# 02_Power.net
KiCad netlist of a schematic drawn in Altium Designer
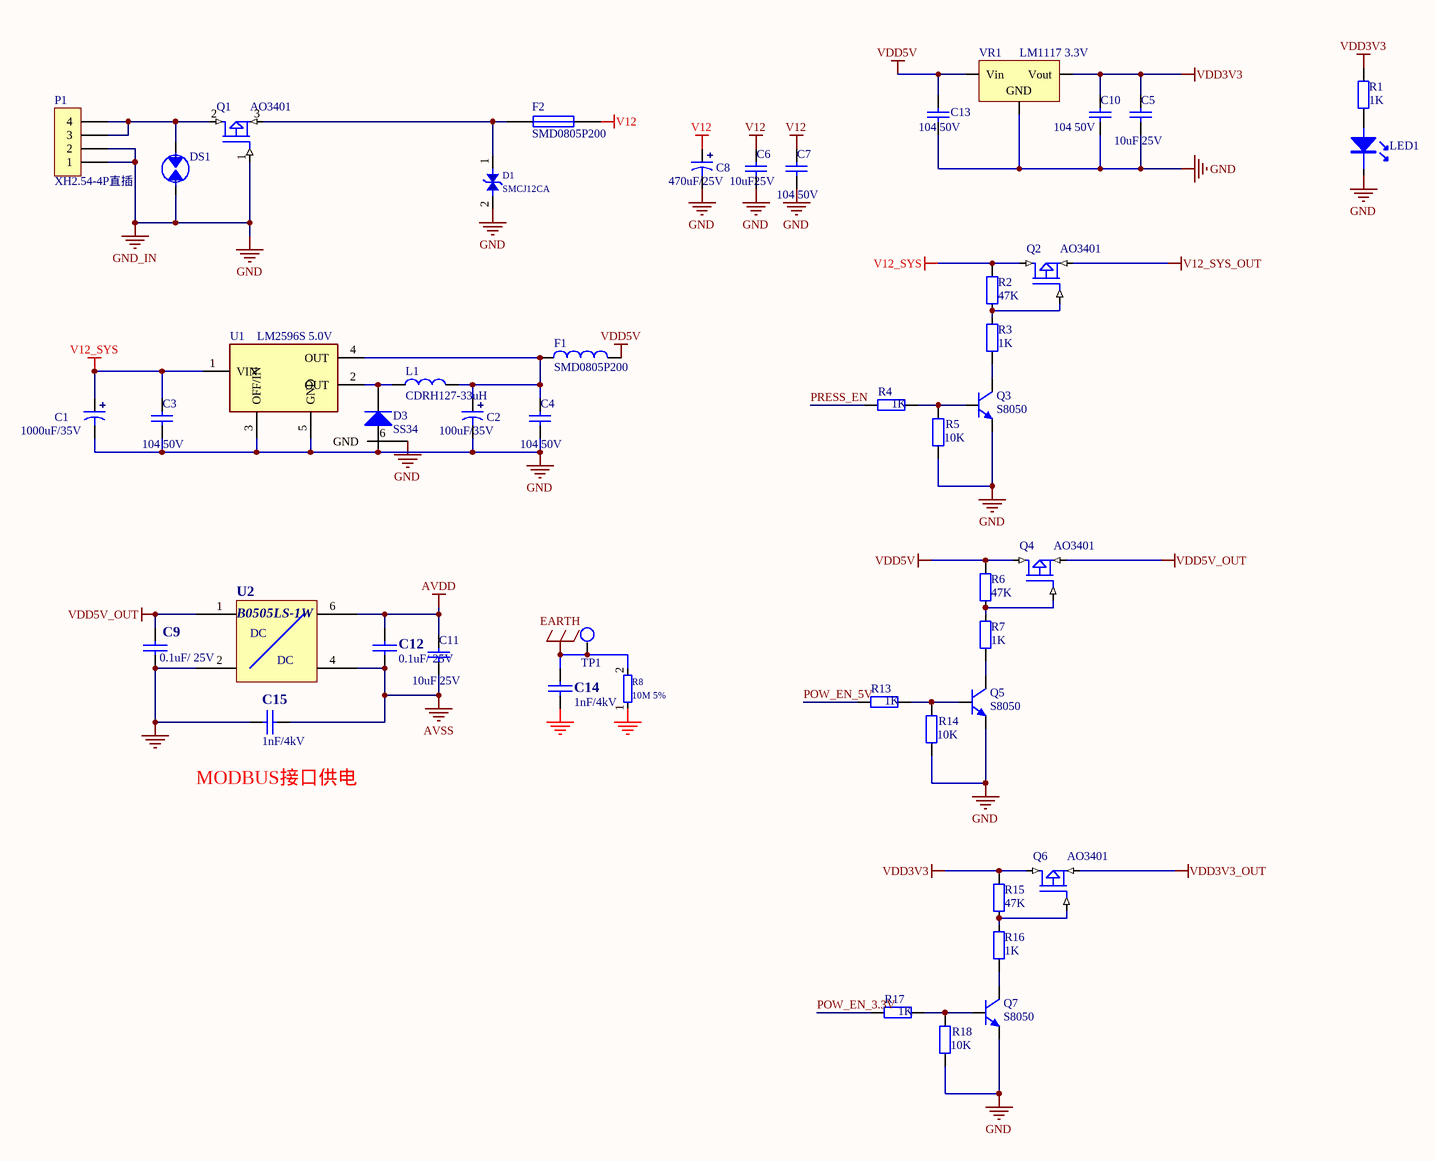
[diagram p0: 02_Power.SchDoc]

(export (version "E")
  (design (tool "Eeschema 10.0.6"))
  (components
    (comp (ref "C1")
      (value "1000uF/35V")
      (footprint "10*16")
      (description "电解电容")
      (libsource (lib "XiaoyI") (part "CAP2"))
    )
    (comp (ref "C2")
      (value "100uF/35V")
      (footprint "6*8")
      (description "电解电容")
      (libsource (lib "XiaoyI") (part "CAP2"))
    )
    (comp (ref "C3")
      (value "104 50V")
      (footprint "SMD-0805C")
      (description "贴片电容 10%")
      (libsource (lib "XiaoyI") (part "CAP4"))
    )
    (comp (ref "C4")
      (value "104 50V")
      (footprint "SMD-0805C")
      (description "贴片电容 10%")
      (libsource (lib "XiaoyI") (part "CAP4"))
    )
    (comp (ref "C5")
      (value "10uF 25V")
      (footprint "SMD-0603C")
      (description "贴片电容 20%")
      (libsource (lib "XiaoyI") (part "CAP4"))
    )
    (comp (ref "C6")
      (value "10uF25V")
      (footprint "SMD-0603C")
      (description "贴片电容 20%")
      (libsource (lib "XiaoyI") (part "CAP4"))
    )
    (comp (ref "C7")
      (value "104 50V")
      (footprint "SMD-0603C")
      (description "贴片电容 20%")
      (libsource (lib "XiaoyI") (part "CAP4"))
    )
    (comp (ref "C8")
      (value "470uF/25V")
      (footprint "8*12")
      (description "电解电容")
      (libsource (lib "XiaoyI") (part "CAP2"))
    )
    (comp (ref "C9")
      (value "0.1uF/ 25V")
      (footprint "0603C")
      (description "Capacitor")
      (libsource (lib "*") (part "CAP"))
    )
    (comp (ref "C10")
      (value "104 50V")
      (footprint "SMD-0603C")
      (description "贴片电容 10%")
      (libsource (lib "XiaoyI") (part "CAP4"))
    )
    (comp (ref "C11")
      (value "10uF 25V")
      (footprint "SMD-0603C")
      (description "贴片电容 20%")
      (libsource (lib "XiaoyI") (part "CAP4"))
    )
    (comp (ref "C12")
      (value "0.1uF/ 25V")
      (footprint "0603C")
      (description "Capacitor")
      (libsource (lib "*") (part "CAP"))
    )
    (comp (ref "C13")
      (value "104 50V")
      (footprint "SMD-0603C")
      (description "贴片电容 10%")
      (libsource (lib "XiaoyI") (part "CAP4"))
    )
    (comp (ref "C14")
      (value "1nF/4kV")
      (footprint "CY1")
      (description "Capacitor")
      (libsource (lib "*") (part "CAP"))
    )
    (comp (ref "C15")
      (value "1nF/4kV")
      (footprint "CY1")
      (description "Capacitor")
      (libsource (lib "*") (part "CAP"))
    )
    (comp (ref "D1") (value "SMCJ12CA") (footprint "SMC") (libsource (lib "*") (part "D_ESD")))
    (comp (ref "D3") (value "SS34") (footprint "SMA") (libsource (lib "Sch_library") (part "DIODE")))
    (comp (ref "DS1")
      (value "UN1812-90CSMD")
      (footprint "SMD-1812")
      (description "气体放电管 90V")
      (libsource (lib "ABB") (part "DISCHARE-1"))
    )
    (comp (ref "F1")
      (value "SMD0805P200")
      (footprint "0805r")
      (description "Inductor")
      (fields (field (name "PUBLISHER") "Altium Limited"))
      (libsource (lib "Miscellaneous Devices") (part "Inductor"))
    )
    (comp (ref "F2")
      (value "SMD0805P200")
      (footprint "PIN-W2/E2.8")
      (description "Fuse")
      (fields (field (name "PUBLISHER") "Altium Limited"))
      (libsource (lib "Miscellaneous Devices") (part "Fuse 1"))
    )
    (comp (ref "L1")
      (value "CDRH127-33uH")
      (footprint "CDRH-127")
      (libsource (lib "Sch_library") (part "IND"))
    )
    (comp (ref "LED1")
      (value "蓝光 3528")
      (footprint "SMD-0603D")
      (description "LED 3528 蓝")
      (libsource (lib "XiaoyI") (part "LED0"))
    )
    (comp (ref "P1") (value "XH2.54-4P直插") (footprint "4X2.54MMZ") (libsource (lib "ABB") (part "SIP-4")))
    (comp (ref "Q1")
      (value "AO3401")
      (footprint "SOT-23")
      (description "MOSFET P")
      (libsource (lib "") (part "MOSFET P_1"))
    )
    (comp (ref "Q2")
      (value "AO3401")
      (footprint "SOT-23")
      (description "MOSFET P")
      (libsource (lib "ABB") (part "MOSFET P"))
    )
    (comp (ref "Q3")
      (value "S8050")
      (footprint "SOT-23")
      (description "NPN")
      (libsource (lib "XiaoyI") (part "NPN-1"))
    )
    (comp (ref "Q4")
      (value "AO3401")
      (footprint "SOT-23")
      (description "MOSFET P")
      (libsource (lib "ABB") (part "MOSFET P"))
    )
    (comp (ref "Q5")
      (value "S8050")
      (footprint "SOT-23")
      (description "NPN")
      (libsource (lib "XiaoyI") (part "NPN-1"))
    )
    (comp (ref "Q6")
      (value "AO3401")
      (footprint "SOT-23")
      (description "MOSFET P")
      (libsource (lib "ABB") (part "MOSFET P"))
    )
    (comp (ref "Q7")
      (value "S8050")
      (footprint "SOT-23")
      (description "NPN")
      (libsource (lib "XiaoyI") (part "NPN-1"))
    )
    (comp (ref "R1")
      (value "1K")
      (footprint "SMD-0603")
      (description "贴片电阻 5%")
      (libsource (lib "XiaoyI") (part "RES2"))
    )
    (comp (ref "R2")
      (value "47K")
      (footprint "SMD-0603")
      (description "贴片电阻 5%")
      (libsource (lib "XiaoyI") (part "RES2"))
    )
    (comp (ref "R3")
      (value "1K")
      (footprint "SMD-0603")
      (description "贴片电阻 5%")
      (libsource (lib "") (part "RES2_1"))
    )
    (comp (ref "R4")
      (value "1K")
      (footprint "SMD-0603")
      (description "贴片电阻 5%")
      (libsource (lib "") (part "RES2_2"))
    )
    (comp (ref "R5")
      (value "10K")
      (footprint "SMD-0603")
      (description "贴片电阻 5%")
      (libsource (lib "") (part "RES2_1"))
    )
    (comp (ref "R6")
      (value "47K")
      (footprint "SMD-0603")
      (description "贴片电阻 5%")
      (libsource (lib "XiaoyI") (part "RES2"))
    )
    (comp (ref "R7")
      (value "1K")
      (footprint "SMD-0603")
      (description "贴片电阻 5%")
      (libsource (lib "") (part "RES2_1"))
    )
    (comp (ref "R8") (value "10M 5%") (footprint "1206r") (libsource (lib "*") (part "RES")))
    (comp (ref "R13")
      (value "1K")
      (footprint "SMD-0603")
      (description "贴片电阻 5%")
      (libsource (lib "") (part "RES2_2"))
    )
    (comp (ref "R14")
      (value "10K")
      (footprint "SMD-0603")
      (description "贴片电阻 5%")
      (libsource (lib "") (part "RES2_1"))
    )
    (comp (ref "R15")
      (value "47K")
      (footprint "SMD-0603")
      (description "贴片电阻 5%")
      (libsource (lib "XiaoyI") (part "RES2"))
    )
    (comp (ref "R16")
      (value "1K")
      (footprint "SMD-0603")
      (description "贴片电阻 5%")
      (libsource (lib "") (part "RES2_1"))
    )
    (comp (ref "R17")
      (value "1K")
      (footprint "SMD-0603")
      (description "贴片电阻 5%")
      (libsource (lib "") (part "RES2_2"))
    )
    (comp (ref "R18")
      (value "10K")
      (footprint "SMD-0603")
      (description "贴片电阻 5%")
      (libsource (lib "") (part "RES2_1"))
    )
    (comp (ref "TP1") (value "TPS") (footprint "tpd") (libsource (lib "stm32") (part "TPS")))
    (comp (ref "U1")
      (value "LM2596S 5.0V")
      (footprint "TO-263-5")
      (libsource (lib "Sch_library") (part "LM2596"))
    )
    (comp (ref "U2") (value "B0505LS-1W") (footprint "HKSXXXXB-1W") (libsource (lib "*") (part "B0505S")))
    (comp (ref "VR1")
      (value "LM1117 3.3V")
      (footprint "SOT223")
      (description "三端稳压器")
      (libsource (lib "XiaoyI") (part "LM1117"))
    )
  )
  (nets
    (net (code "1") (name "/POW_EN_3.3V") (class "Default")
      (node (ref "R17") (pin "1") (pinfunction "1_1") (pintype "passive"))
    )
    (net (code "2") (name "/POW_EN_5V") (class "Default")
      (node (ref "R13") (pin "1") (pinfunction "1_1") (pintype "passive"))
    )
    (net (code "3") (name "/PRESS_EN") (class "Default")
      (node (ref "R4") (pin "1") (pinfunction "1_1") (pintype "passive"))
    )
    (net (code "4") (name "AVDD") (class "Default")
      (node (ref "C11") (pin "2") (pinfunction "2_2") (pintype "passive"))
      (node (ref "C12") (pin "1") (pinfunction "1_1") (pintype "passive"))
      (node (ref "U2") (pin "6") (pintype "passive"))
    )
    (net (code "5") (name "AVSS") (class "Default")
      (node (ref "C11") (pin "1") (pinfunction "1_1") (pintype "passive"))
      (node (ref "C12") (pin "2") (pinfunction "2_2") (pintype "passive"))
      (node (ref "C15") (pin "1") (pinfunction "1_1") (pintype "passive"))
      (node (ref "U2") (pin "4") (pintype "passive"))
    )
    (net (code "6") (name "EARTH") (class "Default")
      (node (ref "C14") (pin "1") (pinfunction "1_1") (pintype "passive"))
      (node (ref "R8") (pin "2") (pinfunction "2_2") (pintype "passive"))
      (node (ref "TP1") (pin "1") (pinfunction "1_1") (pintype "passive"))
    )
    (net (code "7") (name "GND") (class "Default")
      (node (ref "C1") (pin "2") (pinfunction "2_2") (pintype "passive"))
      (node (ref "C10") (pin "1") (pinfunction "1_1") (pintype "passive"))
      (node (ref "C13") (pin "1") (pinfunction "1_1") (pintype "passive"))
      (node (ref "C14") (pin "2") (pinfunction "2_2") (pintype "passive"))
      (node (ref "C15") (pin "2") (pinfunction "2_2") (pintype "passive"))
      (node (ref "C2") (pin "2") (pinfunction "2_2") (pintype "passive"))
      (node (ref "C3") (pin "1") (pinfunction "1_1") (pintype "passive"))
      (node (ref "C4") (pin "1") (pinfunction "1_1") (pintype "passive"))
      (node (ref "C5") (pin "1") (pinfunction "1_1") (pintype "passive"))
      (node (ref "C6") (pin "1") (pinfunction "1_1") (pintype "passive"))
      (node (ref "C7") (pin "1") (pinfunction "1_1") (pintype "passive"))
      (node (ref "C8") (pin "2") (pinfunction "2_2") (pintype "passive"))
      (node (ref "C9") (pin "2") (pinfunction "2_2") (pintype "passive"))
      (node (ref "D1") (pin "2") (pintype "passive"))
      (node (ref "D3") (pin "1") (pinfunction "A_1") (pintype "passive"))
      (node (ref "DS1") (pin "2") (pinfunction "2_2") (pintype "passive"))
      (node (ref "LED1") (pin "2") (pinfunction "2_2") (pintype "passive"))
      (node (ref "P1") (pin "1") (pinfunction "1_1") (pintype "passive"))
      (node (ref "P1") (pin "2") (pinfunction "2_2") (pintype "passive"))
      (node (ref "Q1") (pin "1") (pinfunction "G_1") (pintype "input"))
      (node (ref "Q3") (pin "2") (pinfunction "E_2") (pintype "passive"))
      (node (ref "Q5") (pin "2") (pinfunction "E_2") (pintype "passive"))
      (node (ref "Q7") (pin "2") (pinfunction "E_2") (pintype "passive"))
      (node (ref "R14") (pin "1") (pinfunction "1_1") (pintype "passive"))
      (node (ref "R18") (pin "1") (pinfunction "1_1") (pintype "passive"))
      (node (ref "R5") (pin "1") (pinfunction "1_1") (pintype "passive"))
      (node (ref "R8") (pin "1") (pinfunction "1_1") (pintype "passive"))
      (node (ref "U1") (pin "3") (pinfunction "OFF/IN_3") (pintype "passive"))
      (node (ref "U1") (pin "5") (pinfunction "GND_5") (pintype "passive"))
      (node (ref "U1") (pin "6") (pinfunction "GND_6") (pintype "passive"))
      (node (ref "U2") (pin "2") (pintype "passive"))
      (node (ref "VR1") (pin "1") (pinfunction "GND_1") (pintype "passive"))
    )
    (net (code "8") (name "Net-(C2-Pad1)") (class "Default")
      (node (ref "C2") (pin "1") (pinfunction "1_1") (pintype "passive"))
      (node (ref "C4") (pin "2") (pinfunction "2_2") (pintype "passive"))
      (node (ref "F1") (pin "1") (pinfunction "1_1") (pintype "passive"))
      (node (ref "L1") (pin "2") (pinfunction "2_2") (pintype "passive"))
      (node (ref "U1") (pin "4") (pinfunction "OUT_4") (pintype "passive"))
    )
    (net (code "9") (name "Net-(D3-K)") (class "Default")
      (node (ref "D3") (pin "2") (pinfunction "K_2") (pintype "passive"))
      (node (ref "L1") (pin "1") (pinfunction "1_1") (pintype "passive"))
      (node (ref "U1") (pin "2") (pinfunction "OUT_2") (pintype "passive"))
    )
    (net (code "10") (name "Net-(LED1-Pad1)") (class "Default")
      (node (ref "LED1") (pin "1") (pinfunction "1_1") (pintype "passive"))
      (node (ref "R1") (pin "2") (pinfunction "2_2") (pintype "passive"))
    )
    (net (code "11") (name "Net-(Q1-D)") (class "Default")
      (node (ref "DS1") (pin "1") (pinfunction "1_1") (pintype "passive"))
      (node (ref "P1") (pin "3") (pinfunction "3_3") (pintype "passive"))
      (node (ref "P1") (pin "4") (pinfunction "4_4") (pintype "passive"))
      (node (ref "Q1") (pin "2") (pinfunction "D_2") (pintype "input"))
    )
    (net (code "12") (name "Net-(Q1-S)") (class "Default")
      (node (ref "D1") (pin "1") (pintype "passive"))
      (node (ref "F2") (pin "1") (pinfunction "1_1") (pintype "passive"))
      (node (ref "Q1") (pin "3") (pinfunction "S_3") (pintype "input"))
    )
    (net (code "13") (name "Net-(Q2-G)") (class "Default")
      (node (ref "Q2") (pin "1") (pinfunction "G_1") (pintype "input"))
      (node (ref "R2") (pin "2") (pinfunction "2_2") (pintype "passive"))
      (node (ref "R3") (pin "2") (pinfunction "2_2") (pintype "passive"))
    )
    (net (code "14") (name "Net-(Q3-B)") (class "Default")
      (node (ref "Q3") (pin "1") (pinfunction "B_1") (pintype "passive"))
      (node (ref "R4") (pin "2") (pinfunction "2_2") (pintype "passive"))
      (node (ref "R5") (pin "2") (pinfunction "2_2") (pintype "passive"))
    )
    (net (code "15") (name "Net-(Q3-C)") (class "Default")
      (node (ref "Q3") (pin "3") (pinfunction "C_3") (pintype "passive"))
      (node (ref "R3") (pin "1") (pinfunction "1_1") (pintype "passive"))
    )
    (net (code "16") (name "Net-(Q4-G)") (class "Default")
      (node (ref "Q4") (pin "1") (pinfunction "G_1") (pintype "input"))
      (node (ref "R6") (pin "2") (pinfunction "2_2") (pintype "passive"))
      (node (ref "R7") (pin "2") (pinfunction "2_2") (pintype "passive"))
    )
    (net (code "17") (name "Net-(Q5-B)") (class "Default")
      (node (ref "Q5") (pin "1") (pinfunction "B_1") (pintype "passive"))
      (node (ref "R13") (pin "2") (pinfunction "2_2") (pintype "passive"))
      (node (ref "R14") (pin "2") (pinfunction "2_2") (pintype "passive"))
    )
    (net (code "18") (name "Net-(Q5-C)") (class "Default")
      (node (ref "Q5") (pin "3") (pinfunction "C_3") (pintype "passive"))
      (node (ref "R7") (pin "1") (pinfunction "1_1") (pintype "passive"))
    )
    (net (code "19") (name "Net-(Q6-G)") (class "Default")
      (node (ref "Q6") (pin "1") (pinfunction "G_1") (pintype "input"))
      (node (ref "R15") (pin "2") (pinfunction "2_2") (pintype "passive"))
      (node (ref "R16") (pin "2") (pinfunction "2_2") (pintype "passive"))
    )
    (net (code "20") (name "Net-(Q7-B)") (class "Default")
      (node (ref "Q7") (pin "1") (pinfunction "B_1") (pintype "passive"))
      (node (ref "R17") (pin "2") (pinfunction "2_2") (pintype "passive"))
      (node (ref "R18") (pin "2") (pinfunction "2_2") (pintype "passive"))
    )
    (net (code "21") (name "Net-(Q7-C)") (class "Default")
      (node (ref "Q7") (pin "3") (pinfunction "C_3") (pintype "passive"))
      (node (ref "R16") (pin "1") (pinfunction "1_1") (pintype "passive"))
    )
    (net (code "22") (name "V12") (class "Default")
      (node (ref "C6") (pin "2") (pinfunction "2_2") (pintype "passive"))
      (node (ref "C7") (pin "2") (pinfunction "2_2") (pintype "passive"))
      (node (ref "C8") (pin "1") (pinfunction "1_1") (pintype "passive"))
      (node (ref "F2") (pin "2") (pinfunction "2_2") (pintype "passive"))
    )
    (net (code "23") (name "V12_SYS") (class "Default")
      (node (ref "C1") (pin "1") (pinfunction "1_1") (pintype "passive"))
      (node (ref "C3") (pin "2") (pinfunction "2_2") (pintype "passive"))
      (node (ref "Q2") (pin "2") (pinfunction "D_2") (pintype "input"))
      (node (ref "R2") (pin "1") (pinfunction "1_1") (pintype "passive"))
      (node (ref "U1") (pin "1") (pinfunction "VIN_1") (pintype "passive"))
    )
    (net (code "24") (name "V12_SYS_OUT") (class "Default")
      (node (ref "Q2") (pin "3") (pinfunction "S_3") (pintype "input"))
    )
    (net (code "25") (name "VDD3V3") (class "Default")
      (node (ref "C10") (pin "2") (pinfunction "2_2") (pintype "passive"))
      (node (ref "C5") (pin "2") (pinfunction "2_2") (pintype "passive"))
      (node (ref "Q6") (pin "2") (pinfunction "D_2") (pintype "input"))
      (node (ref "R1") (pin "1") (pinfunction "1_1") (pintype "passive"))
      (node (ref "R15") (pin "1") (pinfunction "1_1") (pintype "passive"))
      (node (ref "VR1") (pin "2") (pinfunction "Vout_2") (pintype "passive"))
    )
    (net (code "26") (name "VDD3V3_OUT") (class "Default")
      (node (ref "Q6") (pin "3") (pinfunction "S_3") (pintype "input"))
    )
    (net (code "27") (name "VDD5V") (class "Default")
      (node (ref "C13") (pin "2") (pinfunction "2_2") (pintype "passive"))
      (node (ref "F1") (pin "2") (pinfunction "2_2") (pintype "passive"))
      (node (ref "Q4") (pin "2") (pinfunction "D_2") (pintype "input"))
      (node (ref "R6") (pin "1") (pinfunction "1_1") (pintype "passive"))
      (node (ref "VR1") (pin "3") (pinfunction "Vin_3") (pintype "passive"))
    )
    (net (code "28") (name "VDD5V_OUT") (class "Default")
      (node (ref "C9") (pin "1") (pinfunction "1_1") (pintype "passive"))
      (node (ref "Q4") (pin "3") (pinfunction "S_3") (pintype "input"))
      (node (ref "U2") (pin "1") (pintype "passive"))
    )
  )
)
